# battery_module.net
KiCad netlist of a schematic drawn in Altium Designer
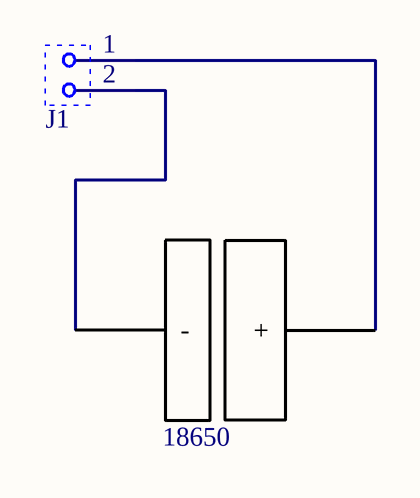
[diagram p0: battery_module.SchDoc]

(export (version "E")
  (design (tool "Eeschema 10.0.6"))
  (components
    (comp (ref "18650")
      (value "18650_cell")
      (footprint "PCBComponent_1")
      (libsource (lib "Schlib1") (part "18650_cell"))
    )
    (comp (ref "J1")
      (value "Molex Microfit")
      (footprint "MicroFit:MICROFIT 1x2 Vertical")
      (libsource (lib "Connectors") (part "Microfit 2x1"))
    )
  )
  (nets
    (net (code "1") (name "Net-(18650-+)") (class "Default")
      (node (ref "18650") (pin "1") (pinfunction "+_1") (pintype "passive"))
      (node (ref "J1") (pin "1") (pintype "passive"))
    )
    (net (code "2") (name "Net-(18650--)") (class "Default")
      (node (ref "18650") (pin "0") (pinfunction "-_0") (pintype "passive"))
      (node (ref "J1") (pin "2") (pintype "passive"))
    )
  )
)
